# TFT_Ticketing_Master.net
KiCad netlist of a schematic drawn in Altium Designer
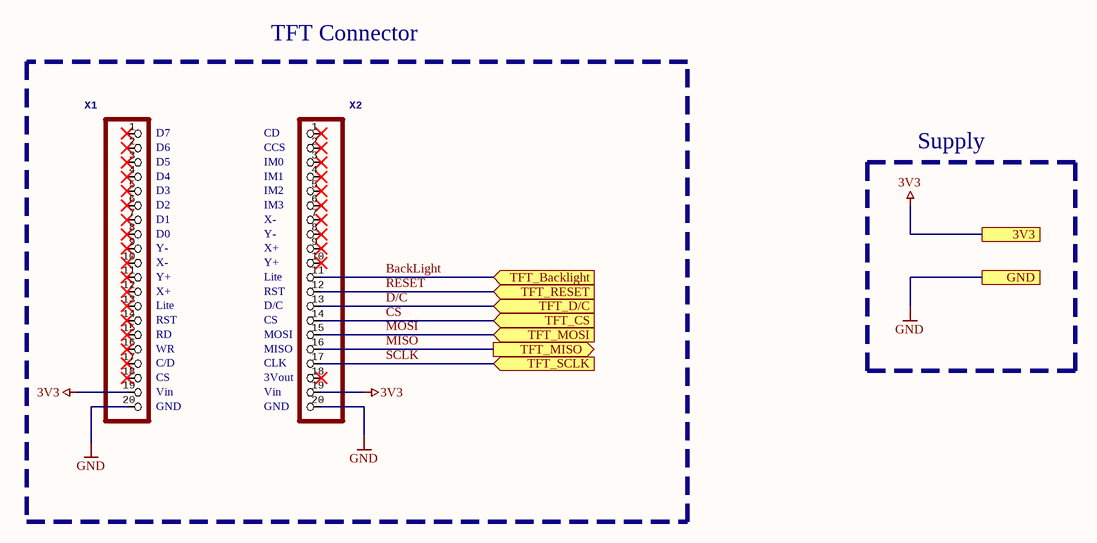
[diagram p0: TFT_Ticketing_Master.SchDoc]

(export (version "E")
  (design (tool "Eeschema 10.0.6"))
  (components
    (comp (ref "X1")
      (value "HEADER-1X20ROUND")
      (footprint "HDR1X20")
      (description "Con_TFT_Gauche")
      (libsource (lib "microbuilder") (part "HEADER-1X20ROUND"))
    )
    (comp (ref "X2")
      (value "HEADER-1X20ROUND")
      (footprint "HDR1X20")
      (description "Con_TFT_Droite")
      (libsource (lib "microbuilder") (part "HEADER-1X20ROUND"))
    )
  )
  (nets
    (net (code "1") (name "/BackLight") (class "Default")
      (node (ref "X2") (pin "11") (pinfunction "11_11") (pintype "passive"))
    )
    (net (code "2") (name "/CS") (class "Default")
      (node (ref "X2") (pin "14") (pinfunction "14_14") (pintype "passive"))
    )
    (net (code "3") (name "/D{slash}C") (class "Default")
      (node (ref "X2") (pin "13") (pinfunction "13_13") (pintype "passive"))
    )
    (net (code "4") (name "/MISO") (class "Default")
      (node (ref "X2") (pin "16") (pinfunction "16_16") (pintype "passive"))
    )
    (net (code "5") (name "/MOSI") (class "Default")
      (node (ref "X2") (pin "15") (pinfunction "15_15") (pintype "passive"))
    )
    (net (code "6") (name "/RESET") (class "Default")
      (node (ref "X2") (pin "12") (pinfunction "12_12") (pintype "passive"))
    )
    (net (code "7") (name "/SCLK") (class "Default")
      (node (ref "X2") (pin "17") (pinfunction "17_17") (pintype "passive"))
    )
    (net (code "8") (name "3V3") (class "Default")
      (node (ref "X1") (pin "19") (pinfunction "19_19") (pintype "passive"))
      (node (ref "X2") (pin "19") (pinfunction "19_19") (pintype "passive"))
    )
    (net (code "9") (name "GND") (class "Default")
      (node (ref "X1") (pin "20") (pinfunction "20_20") (pintype "passive"))
      (node (ref "X2") (pin "20") (pinfunction "20_20") (pintype "passive"))
    )
    (net (code "10") (name "unconnected-(X1-Pad1)") (class "Default")
      (node (ref "X1") (pin "1") (pinfunction "1_1") (pintype "passive+no_connect"))
    )
    (net (code "11") (name "unconnected-(X1-Pad2)") (class "Default")
      (node (ref "X1") (pin "2") (pinfunction "2_2") (pintype "passive+no_connect"))
    )
    (net (code "12") (name "unconnected-(X1-Pad3)") (class "Default")
      (node (ref "X1") (pin "3") (pinfunction "3_3") (pintype "passive+no_connect"))
    )
    (net (code "13") (name "unconnected-(X1-Pad4)") (class "Default")
      (node (ref "X1") (pin "4") (pinfunction "4_4") (pintype "passive+no_connect"))
    )
    (net (code "14") (name "unconnected-(X1-Pad5)") (class "Default")
      (node (ref "X1") (pin "5") (pinfunction "5_5") (pintype "passive+no_connect"))
    )
    (net (code "15") (name "unconnected-(X1-Pad6)") (class "Default")
      (node (ref "X1") (pin "6") (pinfunction "6_6") (pintype "passive+no_connect"))
    )
    (net (code "16") (name "unconnected-(X1-Pad7)") (class "Default")
      (node (ref "X1") (pin "7") (pinfunction "7_7") (pintype "passive+no_connect"))
    )
    (net (code "17") (name "unconnected-(X1-Pad8)") (class "Default")
      (node (ref "X1") (pin "8") (pinfunction "8_8") (pintype "passive+no_connect"))
    )
    (net (code "18") (name "unconnected-(X1-Pad9)") (class "Default")
      (node (ref "X1") (pin "9") (pinfunction "9_9") (pintype "passive+no_connect"))
    )
    (net (code "19") (name "unconnected-(X1-Pad10)") (class "Default")
      (node (ref "X1") (pin "10") (pinfunction "10_10") (pintype "passive+no_connect"))
    )
    (net (code "20") (name "unconnected-(X1-Pad11)") (class "Default")
      (node (ref "X1") (pin "11") (pinfunction "11_11") (pintype "passive+no_connect"))
    )
    (net (code "21") (name "unconnected-(X1-Pad12)") (class "Default")
      (node (ref "X1") (pin "12") (pinfunction "12_12") (pintype "passive+no_connect"))
    )
    (net (code "22") (name "unconnected-(X1-Pad13)") (class "Default")
      (node (ref "X1") (pin "13") (pinfunction "13_13") (pintype "passive+no_connect"))
    )
    (net (code "23") (name "unconnected-(X1-Pad14)") (class "Default")
      (node (ref "X1") (pin "14") (pinfunction "14_14") (pintype "passive+no_connect"))
    )
    (net (code "24") (name "unconnected-(X1-Pad15)") (class "Default")
      (node (ref "X1") (pin "15") (pinfunction "15_15") (pintype "passive+no_connect"))
    )
    (net (code "25") (name "unconnected-(X1-Pad16)") (class "Default")
      (node (ref "X1") (pin "16") (pinfunction "16_16") (pintype "passive+no_connect"))
    )
    (net (code "26") (name "unconnected-(X1-Pad17)") (class "Default")
      (node (ref "X1") (pin "17") (pinfunction "17_17") (pintype "passive+no_connect"))
    )
    (net (code "27") (name "unconnected-(X1-Pad18)") (class "Default")
      (node (ref "X1") (pin "18") (pinfunction "18_18") (pintype "passive+no_connect"))
    )
    (net (code "28") (name "unconnected-(X2-Pad1)") (class "Default")
      (node (ref "X2") (pin "1") (pinfunction "1_1") (pintype "passive+no_connect"))
    )
    (net (code "29") (name "unconnected-(X2-Pad2)") (class "Default")
      (node (ref "X2") (pin "2") (pinfunction "2_2") (pintype "passive+no_connect"))
    )
    (net (code "30") (name "unconnected-(X2-Pad3)") (class "Default")
      (node (ref "X2") (pin "3") (pinfunction "3_3") (pintype "passive+no_connect"))
    )
    (net (code "31") (name "unconnected-(X2-Pad4)") (class "Default")
      (node (ref "X2") (pin "4") (pinfunction "4_4") (pintype "passive+no_connect"))
    )
    (net (code "32") (name "unconnected-(X2-Pad5)") (class "Default")
      (node (ref "X2") (pin "5") (pinfunction "5_5") (pintype "passive+no_connect"))
    )
    (net (code "33") (name "unconnected-(X2-Pad6)") (class "Default")
      (node (ref "X2") (pin "6") (pinfunction "6_6") (pintype "passive+no_connect"))
    )
    (net (code "34") (name "unconnected-(X2-Pad7)") (class "Default")
      (node (ref "X2") (pin "7") (pinfunction "7_7") (pintype "passive+no_connect"))
    )
    (net (code "35") (name "unconnected-(X2-Pad8)") (class "Default")
      (node (ref "X2") (pin "8") (pinfunction "8_8") (pintype "passive+no_connect"))
    )
    (net (code "36") (name "unconnected-(X2-Pad9)") (class "Default")
      (node (ref "X2") (pin "9") (pinfunction "9_9") (pintype "passive+no_connect"))
    )
    (net (code "37") (name "unconnected-(X2-Pad10)") (class "Default")
      (node (ref "X2") (pin "10") (pinfunction "10_10") (pintype "passive+no_connect"))
    )
    (net (code "38") (name "unconnected-(X2-Pad18)") (class "Default")
      (node (ref "X2") (pin "18") (pinfunction "18_18") (pintype "passive+no_connect"))
    )
  )
)
